# Motor_Board.net
KiCad netlist of a schematic drawn in Altium Designer
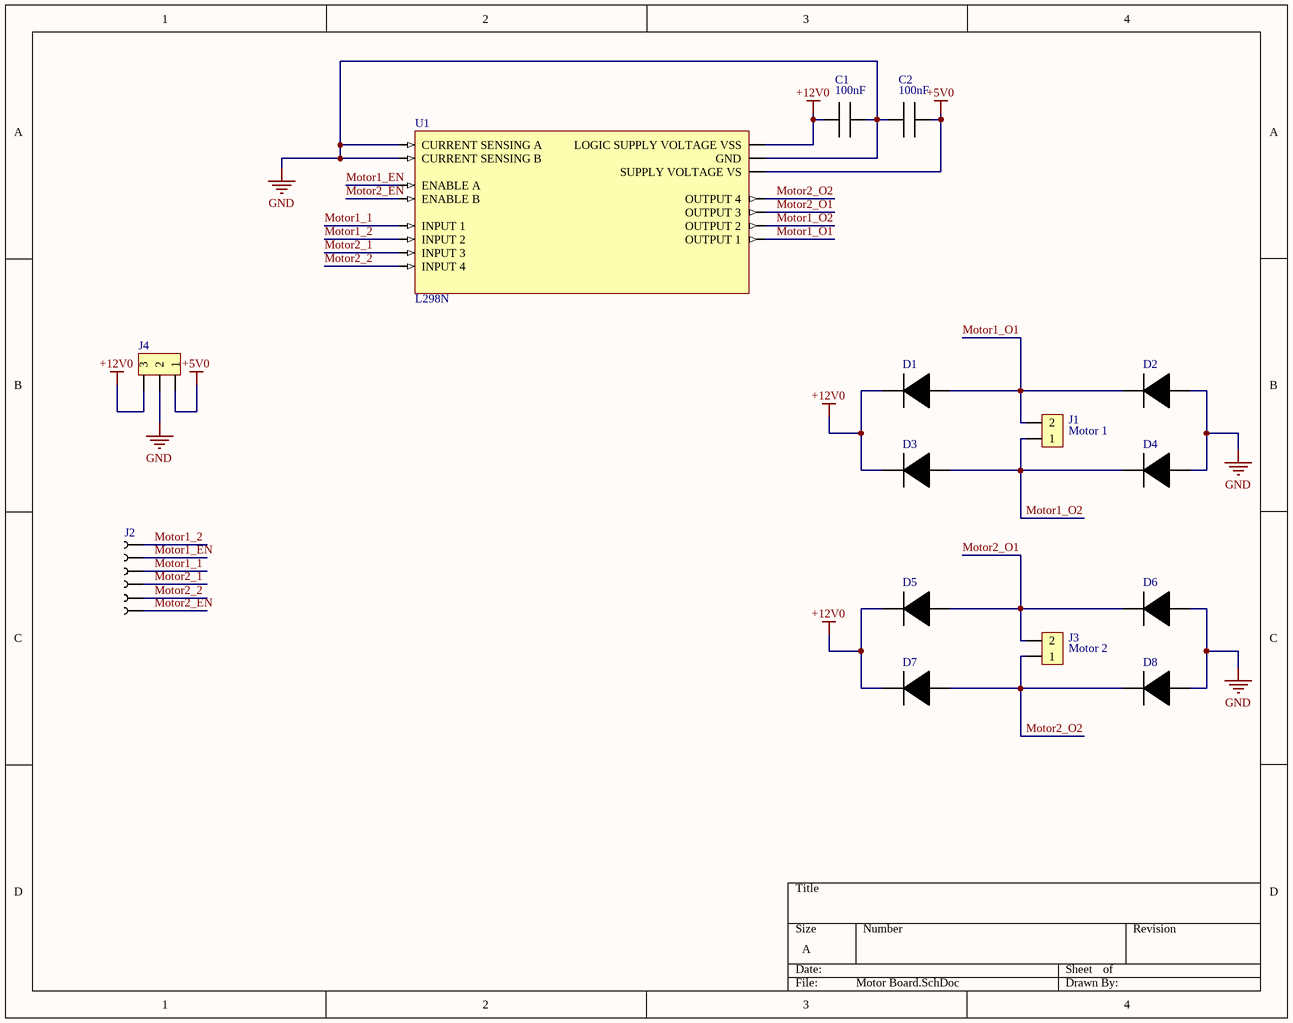
[diagram p0: Motor Board.SchDoc]

(export (version "E")
  (design (tool "Eeschema 10.0.6"))
  (components
    (comp (ref "C1")
      (value "100nF")
      (footprint "Ceramic Cap")
      (fields (field (name "Comment") "Ceramic Capacitor"))
      (libsource (lib "Components") (part "Ceramic Capacitor"))
    )
    (comp (ref "C2")
      (value "100nF")
      (footprint "Ceramic Cap")
      (fields (field (name "Comment") "Ceramic Capacitor"))
      (libsource (lib "Components") (part "Ceramic Capacitor"))
    )
    (comp (ref "D1") (value "Diode") (footprint "2A07") (libsource (lib "Components") (part "Diode")))
    (comp (ref "D2") (value "Diode") (footprint "2A07") (libsource (lib "Components") (part "Diode")))
    (comp (ref "D3") (value "Diode") (footprint "2A07") (libsource (lib "Components") (part "Diode")))
    (comp (ref "D4") (value "Diode") (footprint "2A07") (libsource (lib "Components") (part "Diode")))
    (comp (ref "D5") (value "Diode") (footprint "2A07") (libsource (lib "Components") (part "Diode")))
    (comp (ref "D6") (value "Diode") (footprint "2A07") (libsource (lib "Components") (part "Diode")))
    (comp (ref "D7") (value "Diode") (footprint "2A07") (libsource (lib "Components") (part "Diode")))
    (comp (ref "D8") (value "Diode") (footprint "2A07") (libsource (lib "Components") (part "Diode")))
    (comp (ref "J1")
      (value "Motor 1")
      (footprint "Terminal Block 2-pins")
      (fields (field (name "MF") "Phoenix Contact"))
      (libsource (lib "Components") (part "Terminal Block 2-pins"))
    )
    (comp (ref "J2")
      (value "Headers-6")
      (footprint "Headers 6-pins")
      (libsource (lib "Components") (part "Headers-6"))
    )
    (comp (ref "J3")
      (value "Motor 2")
      (footprint "Terminal Block 2-pins")
      (fields (field (name "MF") "Phoenix Contact"))
      (libsource (lib "Components") (part "Terminal Block 2-pins"))
    )
    (comp (ref "J4")
      (value "Terminal Block 3")
      (footprint "Terminal Block 3")
      (libsource (lib "Components") (part "Terminal Block 3"))
    )
    (comp (ref "U1") (value "L298N") (footprint "L298N") (libsource (lib "Components") (part "L298N")))
  )
  (nets
    (net (code "1") (name "+5V0") (class "Default")
      (node (ref "C2") (pin "2") (pintype "passive"))
      (node (ref "J4") (pin "1") (pinfunction "1_1") (pintype "passive"))
      (node (ref "U1") (pin "4") (pinfunction "SUPPLY_VOLTAGE_VS_4") (pintype "power_in"))
    )
    (net (code "2") (name "+12V0") (class "Default")
      (node (ref "C1") (pin "1") (pintype "passive"))
      (node (ref "D1") (pin "2") (pintype "passive"))
      (node (ref "D3") (pin "2") (pintype "passive"))
      (node (ref "D5") (pin "2") (pintype "passive"))
      (node (ref "D7") (pin "2") (pintype "passive"))
      (node (ref "J4") (pin "3") (pinfunction "3_3") (pintype "passive"))
      (node (ref "U1") (pin "9") (pinfunction "LOGIC_SUPPLY_VOLTAGE_VSS_9") (pintype "power_in"))
    )
    (net (code "3") (name "/Motor1_1") (class "Default")
      (node (ref "J2") (pin "3") (pintype "passive"))
      (node (ref "U1") (pin "5") (pinfunction "INPUT_1_5") (pintype "input"))
    )
    (net (code "4") (name "/Motor1_2") (class "Default")
      (node (ref "J2") (pin "1") (pintype "passive"))
      (node (ref "U1") (pin "7") (pinfunction "INPUT_2_7") (pintype "input"))
    )
    (net (code "5") (name "/Motor1_EN") (class "Default")
      (node (ref "J2") (pin "2") (pintype "passive"))
      (node (ref "U1") (pin "6") (pinfunction "ENABLE_A_6") (pintype "input"))
    )
    (net (code "6") (name "/Motor1_O1") (class "Default")
      (node (ref "D1") (pin "1") (pintype "passive"))
      (node (ref "D2") (pin "2") (pintype "passive"))
      (node (ref "J1") (pin "2") (pinfunction "2_2") (pintype "passive"))
      (node (ref "U1") (pin "2") (pinfunction "OUTPUT_1_2") (pintype "output"))
    )
    (net (code "7") (name "/Motor1_O2") (class "Default")
      (node (ref "D3") (pin "1") (pintype "passive"))
      (node (ref "D4") (pin "2") (pintype "passive"))
      (node (ref "J1") (pin "1") (pinfunction "1_1") (pintype "passive"))
      (node (ref "U1") (pin "3") (pinfunction "OUTPUT_2_3") (pintype "output"))
    )
    (net (code "8") (name "/Motor2_1") (class "Default")
      (node (ref "J2") (pin "4") (pintype "passive"))
      (node (ref "U1") (pin "10") (pinfunction "INPUT_3_10") (pintype "input"))
    )
    (net (code "9") (name "/Motor2_2") (class "Default")
      (node (ref "J2") (pin "5") (pintype "passive"))
      (node (ref "U1") (pin "12") (pinfunction "INPUT_4_12") (pintype "input"))
    )
    (net (code "10") (name "/Motor2_EN") (class "Default")
      (node (ref "J2") (pin "6") (pintype "passive"))
      (node (ref "U1") (pin "11") (pinfunction "ENABLE_B_11") (pintype "input"))
    )
    (net (code "11") (name "/Motor2_O1") (class "Default")
      (node (ref "D5") (pin "1") (pintype "passive"))
      (node (ref "D6") (pin "2") (pintype "passive"))
      (node (ref "J3") (pin "2") (pinfunction "2_2") (pintype "passive"))
      (node (ref "U1") (pin "13") (pinfunction "OUTPUT_3_13") (pintype "output"))
    )
    (net (code "12") (name "/Motor2_O2") (class "Default")
      (node (ref "D7") (pin "1") (pintype "passive"))
      (node (ref "D8") (pin "2") (pintype "passive"))
      (node (ref "J3") (pin "1") (pinfunction "1_1") (pintype "passive"))
      (node (ref "U1") (pin "14") (pinfunction "OUTPUT_4_14") (pintype "output"))
    )
    (net (code "13") (name "GND") (class "Default")
      (node (ref "C1") (pin "2") (pintype "passive"))
      (node (ref "C2") (pin "1") (pintype "passive"))
      (node (ref "D2") (pin "1") (pintype "passive"))
      (node (ref "D4") (pin "1") (pintype "passive"))
      (node (ref "D6") (pin "1") (pintype "passive"))
      (node (ref "D8") (pin "1") (pintype "passive"))
      (node (ref "J4") (pin "2") (pinfunction "2_2") (pintype "passive"))
      (node (ref "U1") (pin "1") (pinfunction "CURRENT_SENSING_A_1") (pintype "input"))
      (node (ref "U1") (pin "15") (pinfunction "CURRENT_SENSING_B_15") (pintype "input"))
      (node (ref "U1") (pin "8") (pinfunction "GND_8") (pintype "power_in"))
    )
  )
)
